# Power.net
KiCad netlist of a schematic drawn in Altium Designer
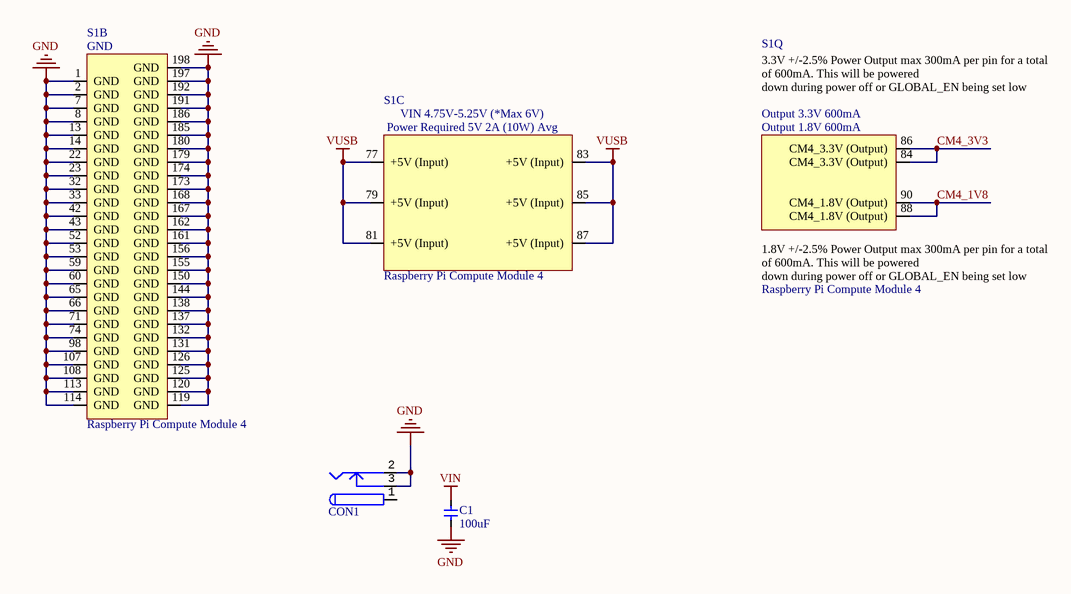
[diagram p0: Power.SchDoc]

(export (version "E")
  (design (tool "Eeschema 10.0.6"))
  (components
    (comp (ref "C1")
      (value "100uF")
      (footprint "1206-CAP")
      (description "Capacitor")
      (libsource (lib "MyPcbLib") (part "电容-1206"))
    )
    (comp (ref "CON1")
      (value "PowerJack_2.5")
      (footprint "KLD_0202")
      (description "DC Power Jack")
      (libsource (lib "KitSprout") (part "PowerJack_2.5"))
    )
    (comp (ref "S1")
      (value "Raspberry Pi Compute Module 4")
      (footprint "CM4-F40C-100DS-0.4v_1.5mm_0mm")
      (description "Raspberry Pi Compute Module 4 by Amornthep Phunsin")
      (libsource (lib "SOM") (part "CM4"))
    )
  )
  (nets
    (net (code "1") (name "/CM4_1V8") (class "Default")
      (node (ref "S1") (pin "88") (pinfunction "CM4_1.8V_(Output)_88") (pintype "power_in"))
      (node (ref "S1") (pin "90") (pinfunction "CM4_1.8V_(Output)_90") (pintype "power_in"))
    )
    (net (code "2") (name "/CM4_3V3") (class "Default")
      (node (ref "S1") (pin "84") (pinfunction "CM4_3.3V_(Output)_84") (pintype "power_in"))
      (node (ref "S1") (pin "86") (pinfunction "CM4_3.3V_(Output)_86") (pintype "power_in"))
    )
    (net (code "3") (name "GND") (class "Default")
      (node (ref "C1") (pin "1") (pinfunction "1_1") (pintype "passive"))
      (node (ref "CON1") (pin "2") (pinfunction "2_2") (pintype "power_in"))
      (node (ref "CON1") (pin "3") (pinfunction "3_3") (pintype "power_in"))
      (node (ref "S1") (pin "1") (pinfunction "GND_1") (pintype "power_in"))
      (node (ref "S1") (pin "107") (pinfunction "GND_107") (pintype "power_in"))
      (node (ref "S1") (pin "108") (pinfunction "GND_108") (pintype "power_in"))
      (node (ref "S1") (pin "113") (pinfunction "GND_113") (pintype "power_in"))
      (node (ref "S1") (pin "114") (pinfunction "GND_114") (pintype "power_in"))
      (node (ref "S1") (pin "119") (pinfunction "GND_119") (pintype "power_in"))
      (node (ref "S1") (pin "120") (pinfunction "GND_120") (pintype "power_in"))
      (node (ref "S1") (pin "125") (pinfunction "GND_125") (pintype "power_in"))
      (node (ref "S1") (pin "126") (pinfunction "GND_126") (pintype "power_in"))
      (node (ref "S1") (pin "13") (pinfunction "GND_13") (pintype "power_in"))
      (node (ref "S1") (pin "131") (pinfunction "GND_131") (pintype "power_in"))
      (node (ref "S1") (pin "132") (pinfunction "GND_132") (pintype "power_in"))
      (node (ref "S1") (pin "137") (pinfunction "GND_137") (pintype "power_in"))
      (node (ref "S1") (pin "138") (pinfunction "GND_138") (pintype "power_in"))
      (node (ref "S1") (pin "14") (pinfunction "GND_14") (pintype "power_in"))
      (node (ref "S1") (pin "144") (pinfunction "GND_144") (pintype "power_in"))
      (node (ref "S1") (pin "150") (pinfunction "GND_150") (pintype "power_in"))
      (node (ref "S1") (pin "155") (pinfunction "GND_155") (pintype "power_in"))
      (node (ref "S1") (pin "156") (pinfunction "GND_156") (pintype "power_in"))
      (node (ref "S1") (pin "161") (pinfunction "GND_161") (pintype "power_in"))
      (node (ref "S1") (pin "162") (pinfunction "GND_162") (pintype "power_in"))
      (node (ref "S1") (pin "167") (pinfunction "GND_167") (pintype "power_in"))
      (node (ref "S1") (pin "168") (pinfunction "GND_168") (pintype "power_in"))
      (node (ref "S1") (pin "173") (pinfunction "GND_173") (pintype "power_in"))
      (node (ref "S1") (pin "174") (pinfunction "GND_174") (pintype "power_in"))
      (node (ref "S1") (pin "179") (pinfunction "GND_179") (pintype "power_in"))
      (node (ref "S1") (pin "180") (pinfunction "GND_180") (pintype "power_in"))
      (node (ref "S1") (pin "185") (pinfunction "GND_185") (pintype "power_in"))
      (node (ref "S1") (pin "186") (pinfunction "GND_186") (pintype "power_in"))
      (node (ref "S1") (pin "191") (pinfunction "GND_191") (pintype "power_in"))
      (node (ref "S1") (pin "192") (pinfunction "GND_192") (pintype "power_in"))
      (node (ref "S1") (pin "197") (pinfunction "GND_197") (pintype "power_in"))
      (node (ref "S1") (pin "198") (pinfunction "GND_198") (pintype "power_in"))
      (node (ref "S1") (pin "2") (pinfunction "GND_2") (pintype "power_in"))
      (node (ref "S1") (pin "22") (pinfunction "GND_22") (pintype "power_in"))
      (node (ref "S1") (pin "23") (pinfunction "GND_23") (pintype "power_in"))
      (node (ref "S1") (pin "32") (pinfunction "GND_32") (pintype "power_in"))
      (node (ref "S1") (pin "33") (pinfunction "GND_33") (pintype "power_in"))
      (node (ref "S1") (pin "42") (pinfunction "GND_42") (pintype "power_in"))
      (node (ref "S1") (pin "43") (pinfunction "GND_43") (pintype "power_in"))
      (node (ref "S1") (pin "52") (pinfunction "GND_52") (pintype "power_in"))
      (node (ref "S1") (pin "53") (pinfunction "GND_53") (pintype "power_in"))
      (node (ref "S1") (pin "59") (pinfunction "GND_59") (pintype "power_in"))
      (node (ref "S1") (pin "60") (pinfunction "GND_60") (pintype "power_in"))
      (node (ref "S1") (pin "65") (pinfunction "GND_65") (pintype "power_in"))
      (node (ref "S1") (pin "66") (pinfunction "GND_66") (pintype "power_in"))
      (node (ref "S1") (pin "7") (pinfunction "GND_7") (pintype "power_in"))
      (node (ref "S1") (pin "71") (pinfunction "GND_71") (pintype "power_in"))
      (node (ref "S1") (pin "74") (pinfunction "GND_74") (pintype "power_in"))
      (node (ref "S1") (pin "8") (pinfunction "GND_8") (pintype "power_in"))
      (node (ref "S1") (pin "98") (pinfunction "GND_98") (pintype "power_in"))
    )
    (net (code "4") (name "VIN") (class "Default")
      (node (ref "C1") (pin "2") (pinfunction "2_2") (pintype "passive"))
    )
    (net (code "5") (name "VUSB") (class "Default")
      (node (ref "S1") (pin "77") (pinfunction "+5V_(Input)_77") (pintype "power_in"))
      (node (ref "S1") (pin "79") (pinfunction "+5V_(Input)_79") (pintype "power_in"))
      (node (ref "S1") (pin "81") (pinfunction "+5V_(Input)_81") (pintype "power_in"))
      (node (ref "S1") (pin "83") (pinfunction "+5V_(Input)_83") (pintype "power_in"))
      (node (ref "S1") (pin "85") (pinfunction "+5V_(Input)_85") (pintype "power_in"))
      (node (ref "S1") (pin "87") (pinfunction "+5V_(Input)_87") (pintype "power_in"))
    )
    (net (code "6") (name "unconnected-(CON1-Pad1)") (class "Default")
      (node (ref "CON1") (pin "1") (pinfunction "1_1") (pintype "power_in"))
    )
  )
)
